# Top_Level.net
KiCad netlist of a schematic drawn in Altium Designer
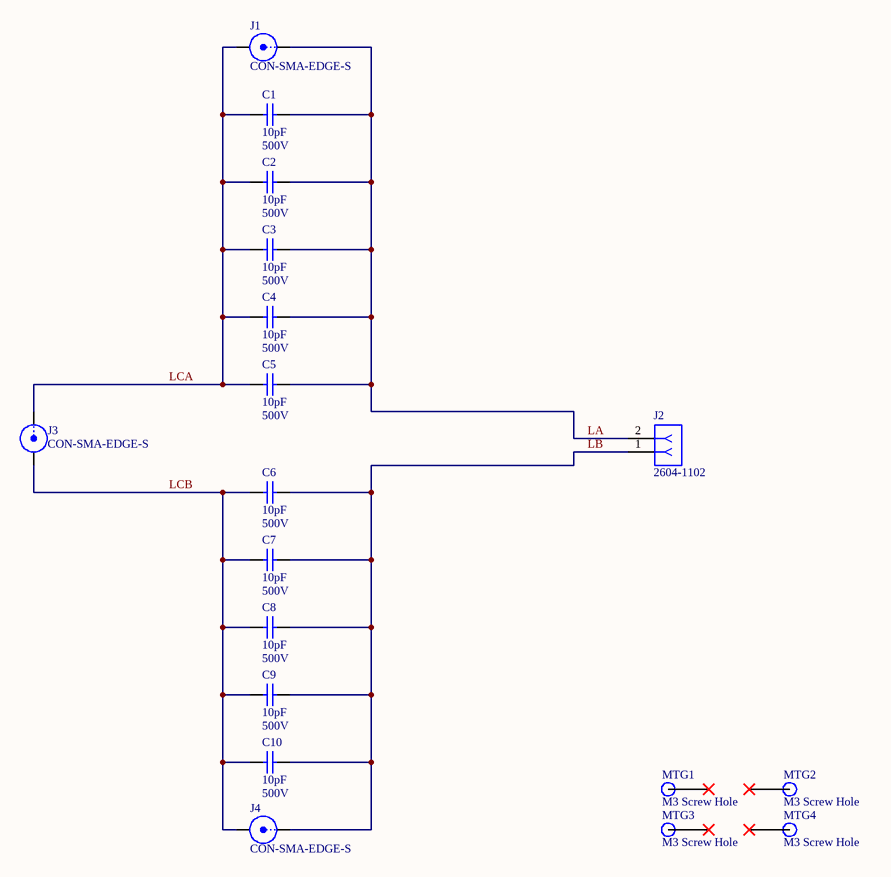
[diagram p0: Top Level.SchDoc]

(export (version "E")
  (design (tool "Eeschema 10.0.6"))
  (components
    (comp (ref "C1")
      (value "10pF")
      (footprint "CAP_1111_ATC 800B")
      (fields (field (name "VOLTAGE") "500V") (field (name "Comment") "800B100JT500XT1K"))
      (libsource (lib "University of Pennsylvania (ESE)") (part "cap"))
    )
    (comp (ref "C2")
      (value "10pF")
      (footprint "CAP_1111_ATC 800B")
      (fields (field (name "VOLTAGE") "500V") (field (name "Comment") "800B100JT500XT1K"))
      (libsource (lib "University of Pennsylvania (ESE)") (part "cap"))
    )
    (comp (ref "C3")
      (value "10pF")
      (footprint "CAP_1111_ATC 800B")
      (fields (field (name "VOLTAGE") "500V") (field (name "Comment") "800B100JT500XT1K"))
      (libsource (lib "University of Pennsylvania (ESE)") (part "cap"))
    )
    (comp (ref "C4")
      (value "10pF")
      (footprint "CAP_1111_ATC 800B")
      (fields (field (name "VOLTAGE") "500V") (field (name "Comment") "800B100JT500XT1K"))
      (libsource (lib "University of Pennsylvania (ESE)") (part "cap"))
    )
    (comp (ref "C5")
      (value "10pF")
      (footprint "CAP_1111_ATC 800B")
      (fields (field (name "VOLTAGE") "500V") (field (name "Comment") "800B100JT500XT1K"))
      (libsource (lib "University of Pennsylvania (ESE)") (part "cap"))
    )
    (comp (ref "C6")
      (value "10pF")
      (footprint "CAP_1111_ATC 800B")
      (fields (field (name "VOLTAGE") "500V") (field (name "Comment") "800B100JT500XT1K"))
      (libsource (lib "University of Pennsylvania (ESE)") (part "cap"))
    )
    (comp (ref "C7")
      (value "10pF")
      (footprint "CAP_1111_ATC 800B")
      (fields (field (name "VOLTAGE") "500V") (field (name "Comment") "800B100JT500XT1K"))
      (libsource (lib "University of Pennsylvania (ESE)") (part "cap"))
    )
    (comp (ref "C8")
      (value "10pF")
      (footprint "CAP_1111_ATC 800B")
      (fields (field (name "VOLTAGE") "500V") (field (name "Comment") "800B100JT500XT1K"))
      (libsource (lib "University of Pennsylvania (ESE)") (part "cap"))
    )
    (comp (ref "C9")
      (value "10pF")
      (footprint "CAP_1111_ATC 800B")
      (fields (field (name "VOLTAGE") "500V") (field (name "Comment") "800B100JT500XT1K"))
      (libsource (lib "University of Pennsylvania (ESE)") (part "cap"))
    )
    (comp (ref "C10")
      (value "10pF")
      (footprint "CAP_1111_ATC 800B")
      (fields (field (name "VOLTAGE") "500V") (field (name "Comment") "800B100JT500XT1K"))
      (libsource (lib "University of Pennsylvania (ESE)") (part "cap"))
    )
    (comp (ref "J1")
      (value "CON-SMA-EDGE-S")
      (footprint "FP-SMA-J-P-H-ST-EM1-MFG")
      (description "Sma Female Connector Jack, Pcb Edge Mount Rohs Compliant: Yes")
      (libsource (lib "University of Pennsylvania (ESE)") (part "RF Connector"))
    )
    (comp (ref "J2")
      (value "2604-1102")
      (footprint "2604-1102_MFG")
      (description "Pcb Terminal Block; Operating Lever; 4 MM²; Pin Spacing 5 Mm; 2-POLE; Push-in Cage Clamp®")
      (libsource (lib "University of Pennsylvania (ESE)") (part "Terminal 1X2"))
    )
    (comp (ref "J3")
      (value "CON-SMA-EDGE-S")
      (footprint "FP-SMA-J-P-H-ST-EM1-MFG")
      (description "Sma Female Connector Jack, Pcb Edge Mount Rohs Compliant: Yes")
      (libsource (lib "University of Pennsylvania (ESE)") (part "RF Connector"))
    )
    (comp (ref "J4")
      (value "CON-SMA-EDGE-S")
      (footprint "FP-SMA-J-P-H-ST-EM1-MFG")
      (description "Sma Female Connector Jack, Pcb Edge Mount Rohs Compliant: Yes")
      (libsource (lib "University of Pennsylvania (ESE)") (part "RF Connector"))
    )
    (comp (ref "MTG1")
      (value "M3 Screw Hole")
      (footprint "M3 Screw Hole-Footprint-1")
      (description "Close clearance Fit for M3 Screw Hole; PCB Mounting for M3 Screw")
      (libsource (lib "University of Pennsylvania (ESE)") (part "M3 Screw Hole-Symbol-1"))
    )
    (comp (ref "MTG2")
      (value "M3 Screw Hole")
      (footprint "M3 Screw Hole-Footprint-1")
      (description "Close clearance Fit for M3 Screw Hole; PCB Mounting for M3 Screw")
      (libsource (lib "University of Pennsylvania (ESE)") (part "M3 Screw Hole-Symbol-1"))
    )
    (comp (ref "MTG3")
      (value "M3 Screw Hole")
      (footprint "M3 Screw Hole-Footprint-1")
      (description "Close clearance Fit for M3 Screw Hole; PCB Mounting for M3 Screw")
      (libsource (lib "University of Pennsylvania (ESE)") (part "M3 Screw Hole-Symbol-1"))
    )
    (comp (ref "MTG4")
      (value "M3 Screw Hole")
      (footprint "M3 Screw Hole-Footprint-1")
      (description "Close clearance Fit for M3 Screw Hole; PCB Mounting for M3 Screw")
      (libsource (lib "University of Pennsylvania (ESE)") (part "M3 Screw Hole-Symbol-1"))
    )
  )
  (nets
    (net (code "1") (name "/LA") (class "Default")
      (node (ref "C1") (pin "2") (pinfunction "2_2") (pintype "passive"))
      (node (ref "C2") (pin "2") (pinfunction "2_2") (pintype "passive"))
      (node (ref "C3") (pin "2") (pinfunction "2_2") (pintype "passive"))
      (node (ref "C4") (pin "2") (pinfunction "2_2") (pintype "passive"))
      (node (ref "C5") (pin "2") (pinfunction "2_2") (pintype "passive"))
      (node (ref "J1") (pin "1") (pinfunction "1_1") (pintype "passive"))
      (node (ref "J2") (pin "2") (pinfunction "2_2") (pintype "passive"))
    )
    (net (code "2") (name "/LB") (class "Default")
      (node (ref "C10") (pin "2") (pinfunction "2_2") (pintype "passive"))
      (node (ref "C6") (pin "2") (pinfunction "2_2") (pintype "passive"))
      (node (ref "C7") (pin "2") (pinfunction "2_2") (pintype "passive"))
      (node (ref "C8") (pin "2") (pinfunction "2_2") (pintype "passive"))
      (node (ref "C9") (pin "2") (pinfunction "2_2") (pintype "passive"))
      (node (ref "J2") (pin "1") (pinfunction "1_1") (pintype "passive"))
      (node (ref "J4") (pin "1") (pinfunction "1_1") (pintype "passive"))
    )
    (net (code "3") (name "/LCA") (class "Default")
      (node (ref "C1") (pin "1") (pinfunction "1_1") (pintype "passive"))
      (node (ref "C2") (pin "1") (pinfunction "1_1") (pintype "passive"))
      (node (ref "C3") (pin "1") (pinfunction "1_1") (pintype "passive"))
      (node (ref "C4") (pin "1") (pinfunction "1_1") (pintype "passive"))
      (node (ref "C5") (pin "1") (pinfunction "1_1") (pintype "passive"))
      (node (ref "J1") (pin "2") (pinfunction "SHELL_2") (pintype "passive"))
      (node (ref "J3") (pin "1") (pinfunction "1_1") (pintype "passive"))
    )
    (net (code "4") (name "/LCB") (class "Default")
      (node (ref "C10") (pin "1") (pinfunction "1_1") (pintype "passive"))
      (node (ref "C6") (pin "1") (pinfunction "1_1") (pintype "passive"))
      (node (ref "C7") (pin "1") (pinfunction "1_1") (pintype "passive"))
      (node (ref "C8") (pin "1") (pinfunction "1_1") (pintype "passive"))
      (node (ref "C9") (pin "1") (pinfunction "1_1") (pintype "passive"))
      (node (ref "J3") (pin "2") (pinfunction "SHELL_2") (pintype "passive"))
      (node (ref "J4") (pin "2") (pinfunction "SHELL_2") (pintype "passive"))
    )
    (net (code "5") (name "unconnected-(MTG1-Pad1)") (class "Default")
      (node (ref "MTG1") (pin "1") (pinfunction "1_1") (pintype "passive+no_connect"))
    )
    (net (code "6") (name "unconnected-(MTG2-Pad1)") (class "Default")
      (node (ref "MTG2") (pin "1") (pinfunction "1_1") (pintype "passive+no_connect"))
    )
    (net (code "7") (name "unconnected-(MTG3-Pad1)") (class "Default")
      (node (ref "MTG3") (pin "1") (pinfunction "1_1") (pintype "passive+no_connect"))
    )
    (net (code "8") (name "unconnected-(MTG4-Pad1)") (class "Default")
      (node (ref "MTG4") (pin "1") (pinfunction "1_1") (pintype "passive+no_connect"))
    )
  )
)
